# zasilacz.net
KiCad netlist of a schematic drawn in EAGLE
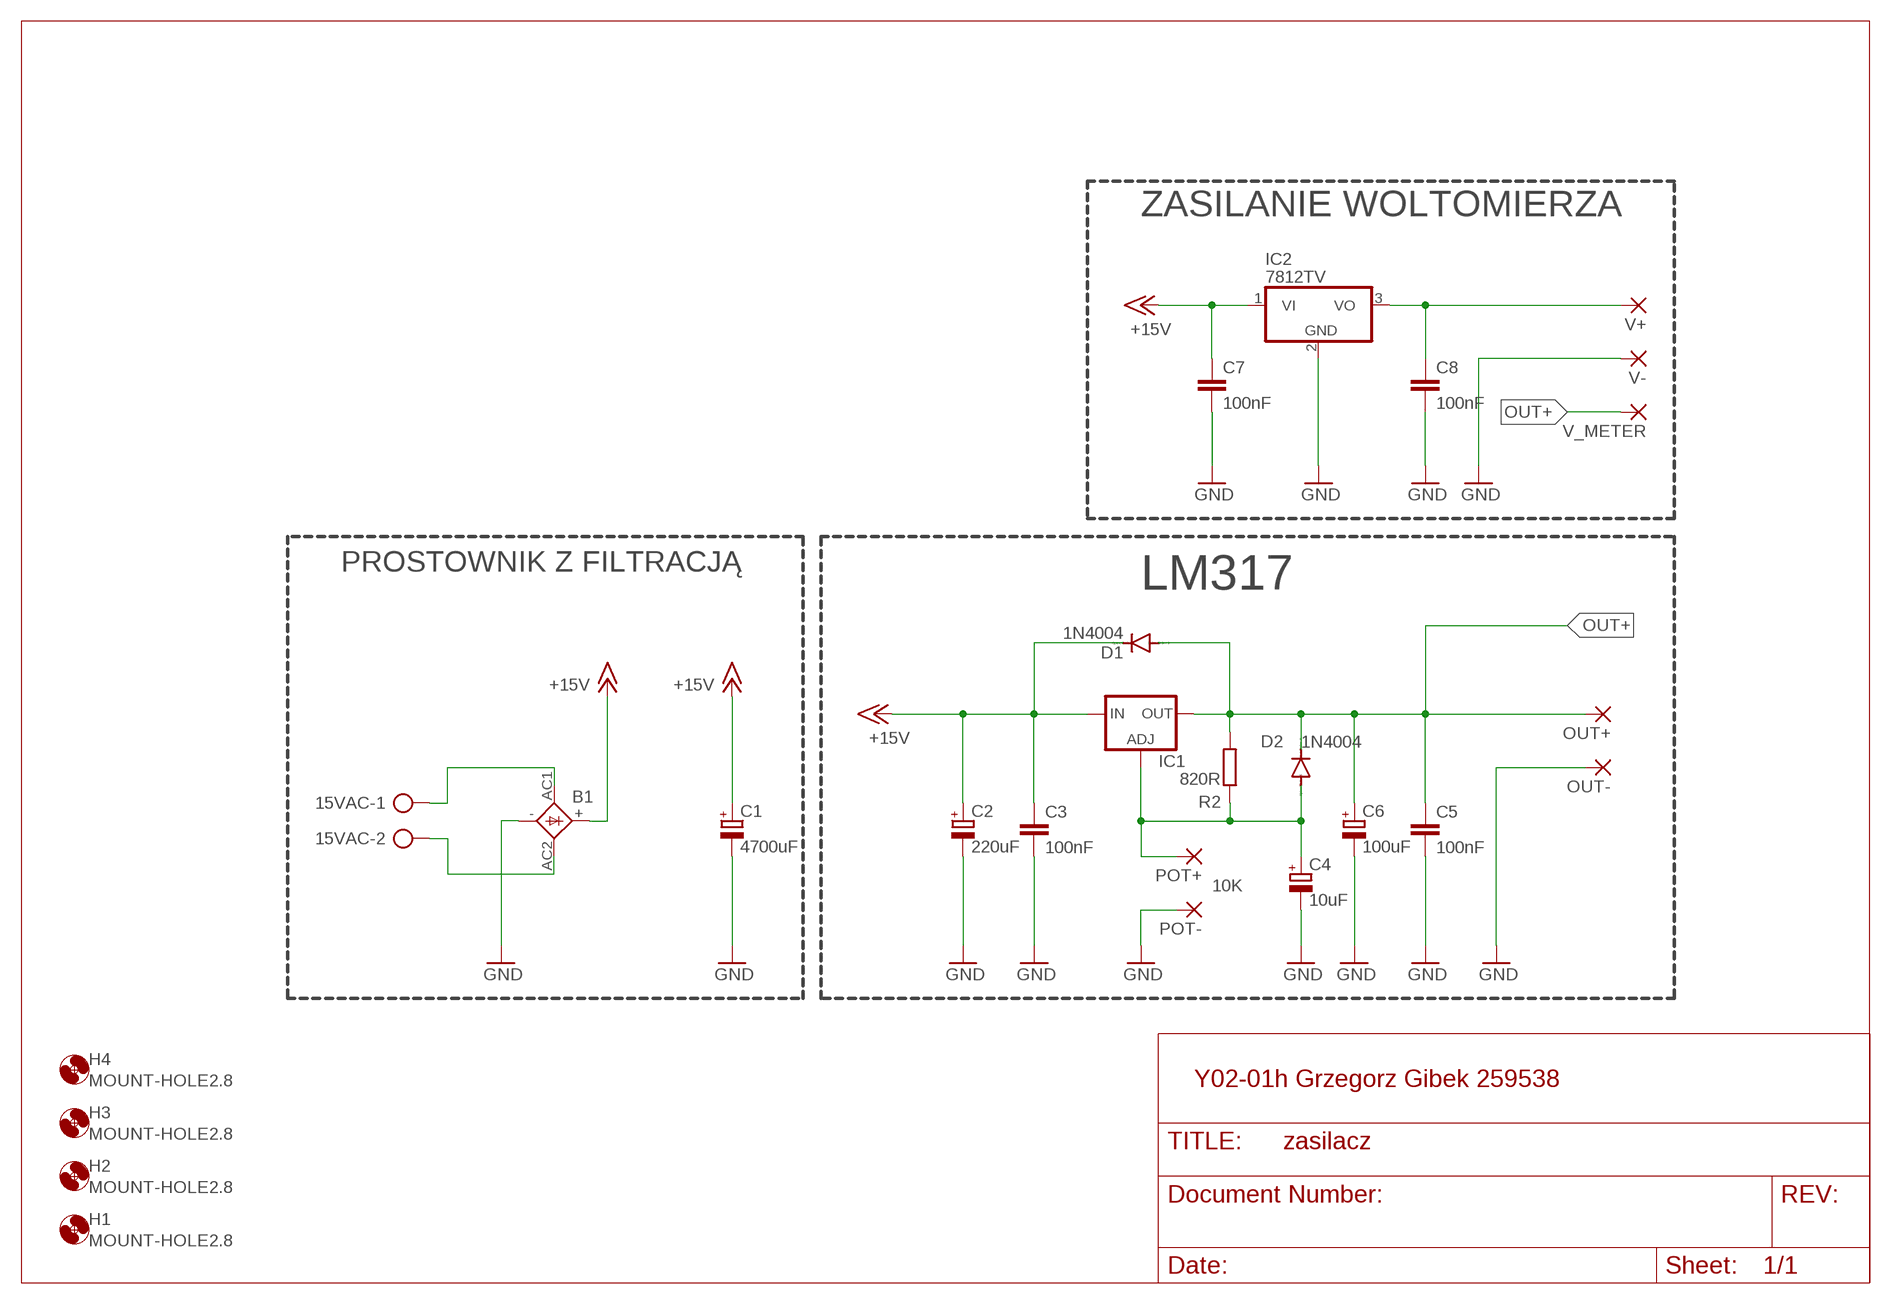
[diagram p0: schematic, sheet 1]

(export (version "E")
  (design (tool "Eeschema 10.0.6"))
  (components
    (comp (ref "15VAC")
      (value "AK500/2")
      (footprint "eagle-import:AK500_2")
      (libsource (lib "eagle-import") (part "AK500/2"))
    )
    (comp (ref "B1")
      (value "2KBP")
      (footprint "eagle-import:2KBP")
      (libsource (lib "eagle-import") (part "2KBP"))
    )
    (comp (ref "C1")
      (value "4700uF")
      (footprint "eagle-import:E7,5-18")
      (libsource (lib "eagle-import") (part "CPOL-EUE7.5-18"))
    )
    (comp (ref "C2")
      (value "220uF")
      (footprint "eagle-import:E5-10,5")
      (libsource (lib "eagle-import") (part "CPOL-EUE5-10.5"))
    )
    (comp (ref "C3")
      (value "100nF")
      (footprint "eagle-import:C050-025X075")
      (libsource (lib "eagle-import") (part "C-EU050-025X075"))
    )
    (comp (ref "C4")
      (value "10uF")
      (footprint "eagle-import:E2,5-6E")
      (libsource (lib "eagle-import") (part "CPOL-EUE2,5-6E"))
    )
    (comp (ref "C5")
      (value "100nF")
      (footprint "eagle-import:C050-025X075")
      (libsource (lib "eagle-import") (part "C-EU050-025X075"))
    )
    (comp (ref "C6")
      (value "100uF")
      (footprint "eagle-import:E5-10,5")
      (libsource (lib "eagle-import") (part "CPOL-EUE5-10.5"))
    )
    (comp (ref "C7")
      (value "100nF")
      (footprint "eagle-import:C050-025X075")
      (libsource (lib "eagle-import") (part "C-EU050-025X075"))
    )
    (comp (ref "C8")
      (value "100nF")
      (footprint "eagle-import:C050-025X075")
      (libsource (lib "eagle-import") (part "C-EU050-025X075"))
    )
    (comp (ref "D1")
      (value "1N4004")
      (footprint "eagle-import:DO41-10")
      (libsource (lib "eagle-import") (part "1N4004"))
    )
    (comp (ref "D2")
      (value "1N4004")
      (footprint "eagle-import:DO41-10")
      (libsource (lib "eagle-import") (part "1N4004"))
    )
    (comp (ref "H1")
      (value "MOUNT-HOLE2.8")
      (footprint "eagle-import:2,8")
      (libsource (lib "eagle-import") (part "MOUNT-HOLE2.8"))
    )
    (comp (ref "H2")
      (value "MOUNT-HOLE2.8")
      (footprint "eagle-import:2,8")
      (libsource (lib "eagle-import") (part "MOUNT-HOLE2.8"))
    )
    (comp (ref "H3")
      (value "MOUNT-HOLE2.8")
      (footprint "eagle-import:2,8")
      (libsource (lib "eagle-import") (part "MOUNT-HOLE2.8"))
    )
    (comp (ref "H4")
      (value "MOUNT-HOLE2.8")
      (footprint "eagle-import:2,8")
      (libsource (lib "eagle-import") (part "MOUNT-HOLE2.8"))
    )
    (comp (ref "IC1")
      (value "LM317TS")
      (footprint "eagle-import:317TS")
      (libsource (lib "eagle-import") (part "LM317TS"))
    )
    (comp (ref "IC2")
      (value "7812TV")
      (footprint "eagle-import:TO220V")
      (libsource (lib "eagle-import") (part "78TV12"))
    )
    (comp (ref "OUT+")
      (value "3,81/1,4")
      (footprint "eagle-import:3,81_1,4")
      (libsource (lib "eagle-import") (part "3,81/1,4"))
    )
    (comp (ref "OUT-")
      (value "3,81/1,4")
      (footprint "eagle-import:3,81_1,4")
      (libsource (lib "eagle-import") (part "3,81/1,4"))
    )
    (comp (ref "POT+")
      (value "3,81/1,4")
      (footprint "eagle-import:3,81_1,4")
      (libsource (lib "eagle-import") (part "3,81/1,4"))
    )
    (comp (ref "POT-")
      (value "3,81/1,4")
      (footprint "eagle-import:3,81_1,4")
      (libsource (lib "eagle-import") (part "3,81/1,4"))
    )
    (comp (ref "R2")
      (value "820R")
      (footprint "eagle-import:0204_7")
      (libsource (lib "eagle-import") (part "R-EU_0204/7"))
    )
    (comp (ref "V+")
      (value "3,81/1,4")
      (footprint "eagle-import:3,81_1,4")
      (libsource (lib "eagle-import") (part "3,81/1,4"))
    )
    (comp (ref "V-")
      (value "3,81/1,4")
      (footprint "eagle-import:3,81_1,4")
      (libsource (lib "eagle-import") (part "3,81/1,4"))
    )
    (comp (ref "V_METER")
      (value "3,81/1,4")
      (footprint "eagle-import:3,81_1,4")
      (libsource (lib "eagle-import") (part "3,81/1,4"))
    )
  )
  (nets
    (net (code "1") (name "+15V") (class "Default")
      (node (ref "B1") (pin "+") (pinfunction "+_+") (pintype "passive"))
      (node (ref "C1") (pin "+") (pinfunction "+_+") (pintype "passive"))
      (node (ref "C2") (pin "+") (pinfunction "+_+") (pintype "passive"))
      (node (ref "C3") (pin "1") (pinfunction "1_1") (pintype "passive"))
      (node (ref "C7") (pin "1") (pinfunction "1_1") (pintype "passive"))
      (node (ref "D1") (pin "C") (pinfunction "C_C") (pintype "passive"))
      (node (ref "IC1") (pin "3") (pinfunction "IN_3") (pintype "input"))
      (node (ref "IC2") (pin "1") (pinfunction "VI_1") (pintype "input"))
    )
    (net (code "2") (name "GND") (class "Default")
      (node (ref "B1") (pin "-") (pinfunction "-_-") (pintype "passive"))
      (node (ref "C1") (pin "-") (pinfunction "-_-") (pintype "passive"))
      (node (ref "C2") (pin "-") (pinfunction "-_-") (pintype "passive"))
      (node (ref "C3") (pin "2") (pinfunction "2_2") (pintype "passive"))
      (node (ref "C4") (pin "-") (pinfunction "-_-") (pintype "passive"))
      (node (ref "C5") (pin "2") (pinfunction "2_2") (pintype "passive"))
      (node (ref "C6") (pin "-") (pinfunction "-_-") (pintype "passive"))
      (node (ref "C7") (pin "2") (pinfunction "2_2") (pintype "passive"))
      (node (ref "C8") (pin "2") (pinfunction "2_2") (pintype "passive"))
      (node (ref "IC2") (pin "2") (pinfunction "GND_2") (pintype "passive"))
      (node (ref "OUT-") (pin "1") (pinfunction "P_1") (pintype "passive"))
      (node (ref "POT-") (pin "1") (pinfunction "P_1") (pintype "passive"))
      (node (ref "V-") (pin "1") (pinfunction "P_1") (pintype "passive"))
    )
    (net (code "3") (name "Net-(15VACA-KL)") (class "Default")
      (node (ref "15VAC") (pin "1") (pinfunction "KL_1") (pintype "passive"))
      (node (ref "B1") (pin "AC1") (pinfunction "AC1_AC1") (pintype "passive"))
    )
    (net (code "4") (name "Net-(15VACB-KL)") (class "Default")
      (node (ref "15VAC") (pin "2") (pinfunction "KL_2") (pintype "passive"))
      (node (ref "B1") (pin "AC2") (pinfunction "AC2_AC2") (pintype "passive"))
    )
    (net (code "5") (name "Net-(IC1-ADJ)") (class "Default")
      (node (ref "C4") (pin "+") (pinfunction "+_+") (pintype "passive"))
      (node (ref "D2") (pin "A") (pinfunction "A_A") (pintype "passive"))
      (node (ref "IC1") (pin "1") (pinfunction "ADJ_1") (pintype "input"))
      (node (ref "POT+") (pin "1") (pinfunction "P_1") (pintype "passive"))
      (node (ref "R2") (pin "1") (pinfunction "1_1") (pintype "passive"))
    )
    (net (code "6") (name "Net-(IC2-VO)") (class "Default")
      (node (ref "C8") (pin "1") (pinfunction "1_1") (pintype "passive"))
      (node (ref "IC2") (pin "3") (pinfunction "VO_3") (pintype "passive"))
      (node (ref "V+") (pin "1") (pinfunction "P_1") (pintype "passive"))
    )
    (net (code "7") (name "OUT+") (class "Default")
      (node (ref "C5") (pin "1") (pinfunction "1_1") (pintype "passive"))
      (node (ref "C6") (pin "+") (pinfunction "+_+") (pintype "passive"))
      (node (ref "D1") (pin "A") (pinfunction "A_A") (pintype "passive"))
      (node (ref "D2") (pin "C") (pinfunction "C_C") (pintype "passive"))
      (node (ref "IC1") (pin "2") (pinfunction "OUT_2") (pintype "passive"))
      (node (ref "OUT+") (pin "1") (pinfunction "P_1") (pintype "passive"))
      (node (ref "R2") (pin "2") (pinfunction "2_2") (pintype "passive"))
      (node (ref "V_METER") (pin "1") (pinfunction "P_1") (pintype "passive"))
    )
  )
)
